# CANNode.net
KiCad netlist of a schematic drawn in EAGLE
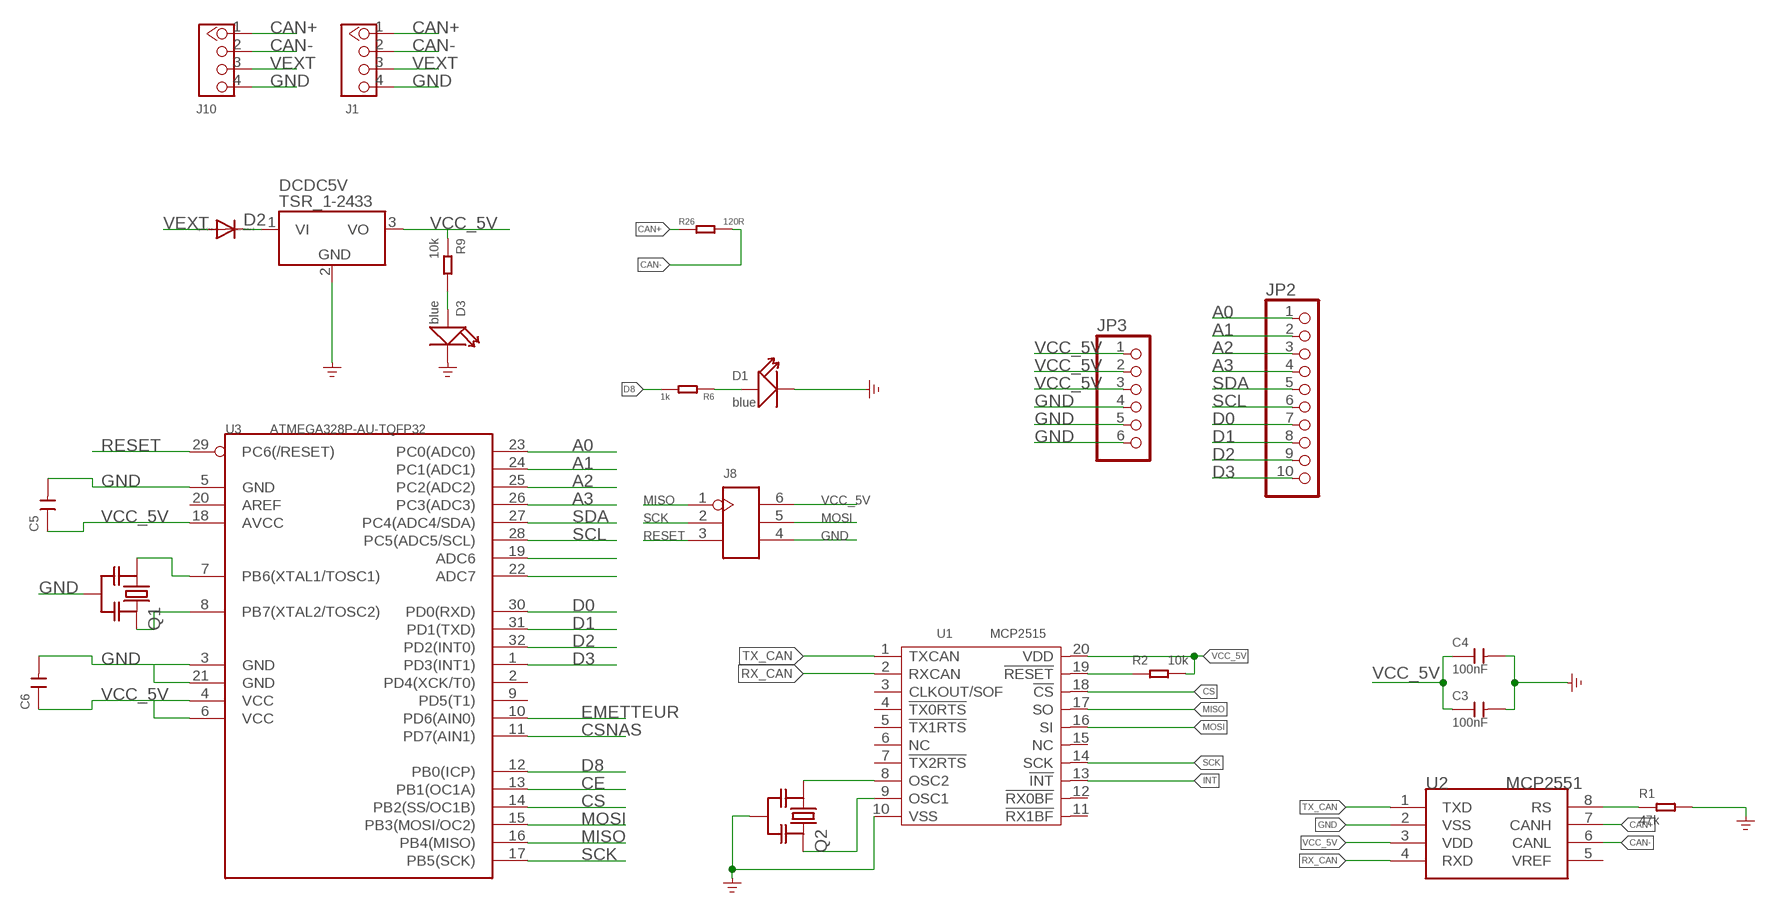
[diagram p0: schematic, sheet 1]

(export (version "E")
  (design (tool "Eeschema 10.0.6"))
  (components
    (comp (ref "C3")
      (value "100nF")
      (footprint "eagle-import:C0805")
      (libsource (lib "eagle-import") (part "CAP-0805"))
    )
    (comp (ref "C4")
      (value "100nF")
      (footprint "eagle-import:C0805")
      (libsource (lib "eagle-import") (part "CAP-0805"))
    )
    (comp (ref "C5")
      (value "CAP-0805")
      (footprint "eagle-import:C0805")
      (libsource (lib "eagle-import") (part "CAP-0805"))
    )
    (comp (ref "C6")
      (value "CAP-0805")
      (footprint "eagle-import:C0805")
      (libsource (lib "eagle-import") (part "CAP-0805"))
    )
    (comp (ref "D1")
      (value "blue")
      (footprint "eagle-import:LED-0805")
      (libsource (lib "eagle-import") (part "LED-0805"))
    )
    (comp (ref "D2")
      (value "DIODE-SOD323-W")
      (footprint "eagle-import:SOD323-W")
      (libsource (lib "eagle-import") (part "DIODE-SOD323-W"))
    )
    (comp (ref "D3")
      (value "blue")
      (footprint "eagle-import:LED-0805")
      (libsource (lib "eagle-import") (part "LED-0805"))
    )
    (comp (ref "DCDC5V")
      (value "TSR_1-2433")
      (footprint "eagle-import:TSR-1")
      (libsource (lib "eagle-import") (part "TSR_1-2433"))
    )
    (comp (ref "J1")
      (value "320110033")
      (footprint "eagle-import:HW4-2.0")
      (libsource (lib "eagle-import") (part "GROVE-CONNECTOR-DIP-2.0"))
    )
    (comp (ref "J8")
      (value "HEADER-2X3P-2.54")
      (footprint "eagle-import:H2X3-2.54")
      (libsource (lib "eagle-import") (part "HEADER-2X3P-2.54"))
    )
    (comp (ref "J10")
      (value "320110033")
      (footprint "eagle-import:HW4-2.0")
      (libsource (lib "eagle-import") (part "GROVE-CONNECTOR-DIP-2.0"))
    )
    (comp (ref "JP2")
      (value "PINHD-1X10")
      (footprint "eagle-import:1X10")
      (libsource (lib "eagle-import") (part "PINHD-1X10"))
    )
    (comp (ref "JP3")
      (value "PINHD-1X6")
      (footprint "eagle-import:1X06")
      (libsource (lib "eagle-import") (part "PINHD-1X6"))
    )
    (comp (ref "Q1")
      (value "RESONATOR-MURATACST_CE")
      (footprint "eagle-import:RESONATOR_MURATA2")
      (libsource (lib "eagle-import") (part "RESONATOR-MURATACST_CE"))
    )
    (comp (ref "Q2")
      (value "RESONATOR-MURATACST_CE")
      (footprint "eagle-import:RESONATOR_MURATA2")
      (libsource (lib "eagle-import") (part "RESONATOR-MURATACST_CE"))
    )
    (comp (ref "R1")
      (value "47k")
      (footprint "eagle-import:R0805")
      (libsource (lib "eagle-import") (part "Seeed-OPL-Resistor_RES-0805"))
    )
    (comp (ref "R2")
      (value "10k")
      (footprint "eagle-import:R0603")
      (libsource (lib "eagle-import") (part "RES-0603"))
    )
    (comp (ref "R6")
      (value "1k")
      (footprint "eagle-import:R0805")
      (libsource (lib "eagle-import") (part "Seeed-OPL-Resistor_RES-0805"))
    )
    (comp (ref "R9")
      (value "10k")
      (footprint "eagle-import:R0805")
      (libsource (lib "eagle-import") (part "Seeed-OPL-Resistor_RES-0805"))
    )
    (comp (ref "R26")
      (value "120R")
      (footprint "eagle-import:R0805")
      (libsource (lib "eagle-import") (part "Seeed-OPL-Resistor_RES-0805"))
    )
    (comp (ref "U1")
      (value "MCP2515")
      (footprint "eagle-import:TSSOP20-0.65-6.5X4.4MM")
      (libsource (lib "eagle-import") (part "MCP2515'ST'"))
    )
    (comp (ref "U2")
      (value "MCP2551")
      (footprint "eagle-import:SOIC8-6.0")
      (libsource (lib "eagle-import") (part "MCP2551-SOIC8"))
    )
    (comp (ref "U3")
      (value "ATMEGA328P-AU-TQFP32")
      (footprint "eagle-import:TQFP32-0.8-7X7MM")
      (fields (field (name "MPN") "ATMEGA328P-AU"))
      (libsource (lib "eagle-import") (part "MCU-ATMEGA328P-AU(TQFP32)"))
    )
  )
  (nets
    (net (code "1") (name "A0") (class "Default")
      (node (ref "JP2") (pin "1") (pinfunction "1_1") (pintype "passive"))
      (node (ref "U3") (pin "23") (pinfunction "PC0(ADC0)_23") (pintype "bidirectional"))
    )
    (net (code "2") (name "A1") (class "Default")
      (node (ref "JP2") (pin "2") (pinfunction "2_2") (pintype "passive"))
      (node (ref "U3") (pin "24") (pinfunction "PC1(ADC1)_24") (pintype "bidirectional"))
    )
    (net (code "3") (name "A2") (class "Default")
      (node (ref "JP2") (pin "3") (pinfunction "3_3") (pintype "passive"))
      (node (ref "U3") (pin "25") (pinfunction "PC2(ADC2)_25") (pintype "bidirectional"))
    )
    (net (code "4") (name "A3") (class "Default")
      (node (ref "JP2") (pin "4") (pinfunction "4_4") (pintype "passive"))
      (node (ref "U3") (pin "26") (pinfunction "PC3(ADC3)_26") (pintype "bidirectional"))
    )
    (net (code "5") (name "CAN+") (class "Default")
      (node (ref "J1") (pin "1") (pinfunction "1_1") (pintype "bidirectional"))
      (node (ref "J10") (pin "1") (pinfunction "1_1") (pintype "bidirectional"))
      (node (ref "R26") (pin "1") (pinfunction "1_1") (pintype "passive"))
      (node (ref "U2") (pin "7") (pinfunction "CANH_7") (pintype "bidirectional"))
    )
    (net (code "6") (name "CAN-") (class "Default")
      (node (ref "J1") (pin "2") (pinfunction "2_2") (pintype "bidirectional"))
      (node (ref "J10") (pin "2") (pinfunction "2_2") (pintype "bidirectional"))
      (node (ref "R26") (pin "2") (pinfunction "2_2") (pintype "passive"))
      (node (ref "U2") (pin "6") (pinfunction "CANL_6") (pintype "bidirectional"))
    )
    (net (code "7") (name "CE") (class "Default")
      (node (ref "U3") (pin "13") (pinfunction "PB1(OC1A)_13") (pintype "bidirectional"))
    )
    (net (code "8") (name "CS") (class "Default")
      (node (ref "U1") (pin "18") (pinfunction "~{CS}_18") (pintype "bidirectional"))
      (node (ref "U3") (pin "14") (pinfunction "PB2(SS/OC1B)_14") (pintype "bidirectional"))
    )
    (net (code "9") (name "CSNAS") (class "Default")
      (node (ref "U3") (pin "11") (pinfunction "PD7(AIN1)_11") (pintype "bidirectional"))
    )
    (net (code "10") (name "D0") (class "Default")
      (node (ref "JP2") (pin "7") (pinfunction "7_7") (pintype "passive"))
      (node (ref "U3") (pin "30") (pinfunction "PD0(RXD)_30") (pintype "bidirectional"))
    )
    (net (code "11") (name "D1") (class "Default")
      (node (ref "JP2") (pin "8") (pinfunction "8_8") (pintype "passive"))
      (node (ref "U3") (pin "31") (pinfunction "PD1(TXD)_31") (pintype "bidirectional"))
    )
    (net (code "12") (name "D2") (class "Default")
      (node (ref "JP2") (pin "9") (pinfunction "9_9") (pintype "passive"))
      (node (ref "U3") (pin "32") (pinfunction "PD2(INT0)_32") (pintype "bidirectional"))
    )
    (net (code "13") (name "D3") (class "Default")
      (node (ref "JP2") (pin "10") (pinfunction "10_10") (pintype "passive"))
      (node (ref "U3") (pin "1") (pinfunction "PD3(INT1)_1") (pintype "bidirectional"))
    )
    (net (code "14") (name "D8") (class "Default")
      (node (ref "R6") (pin "2") (pinfunction "2_2") (pintype "passive"))
      (node (ref "U3") (pin "12") (pinfunction "PB0(ICP)_12") (pintype "bidirectional"))
    )
    (net (code "15") (name "EMETTEUR") (class "Default")
      (node (ref "U3") (pin "10") (pinfunction "PD6(AIN0)_10") (pintype "bidirectional"))
    )
    (net (code "16") (name "GND") (class "Default")
      (node (ref "C3") (pin "2") (pinfunction "2_2") (pintype "passive"))
      (node (ref "C4") (pin "2") (pinfunction "2_2") (pintype "passive"))
      (node (ref "C5") (pin "2") (pinfunction "2_2") (pintype "passive"))
      (node (ref "C6") (pin "2") (pinfunction "2_2") (pintype "passive"))
      (node (ref "D1") (pin "-") (pinfunction "-_-") (pintype "passive"))
      (node (ref "D3") (pin "-") (pinfunction "-_-") (pintype "passive"))
      (node (ref "DCDC5V") (pin "2") (pinfunction "GND_2") (pintype "power_in"))
      (node (ref "J1") (pin "4") (pinfunction "4_4") (pintype "bidirectional"))
      (node (ref "J10") (pin "4") (pinfunction "4_4") (pintype "bidirectional"))
      (node (ref "J8") (pin "4") (pinfunction "4_4") (pintype "bidirectional"))
      (node (ref "JP3") (pin "4") (pinfunction "4_4") (pintype "passive"))
      (node (ref "JP3") (pin "5") (pinfunction "5_5") (pintype "passive"))
      (node (ref "JP3") (pin "6") (pinfunction "6_6") (pintype "passive"))
      (node (ref "Q1") (pin "2") (pinfunction "2_2") (pintype "passive"))
      (node (ref "Q2") (pin "2") (pinfunction "2_2") (pintype "passive"))
      (node (ref "R1") (pin "2") (pinfunction "2_2") (pintype "passive"))
      (node (ref "U1") (pin "10") (pinfunction "VSS_10") (pintype "bidirectional"))
      (node (ref "U2") (pin "2") (pinfunction "VSS_2") (pintype "bidirectional"))
      (node (ref "U3") (pin "21") (pinfunction "GND_21") (pintype "bidirectional"))
      (node (ref "U3") (pin "3") (pinfunction "GND_3") (pintype "bidirectional"))
      (node (ref "U3") (pin "5") (pinfunction "GND_5") (pintype "bidirectional"))
    )
    (net (code "17") (name "INT") (class "Default")
      (node (ref "U1") (pin "13") (pinfunction "~{INT}_13") (pintype "bidirectional"))
    )
    (net (code "18") (name "MISO") (class "Default")
      (node (ref "J8") (pin "1") (pinfunction "1_1") (pintype "bidirectional"))
      (node (ref "U1") (pin "17") (pinfunction "SO_17") (pintype "bidirectional"))
      (node (ref "U3") (pin "16") (pinfunction "PB4(MISO)_16") (pintype "bidirectional"))
    )
    (net (code "19") (name "MOSI") (class "Default")
      (node (ref "J8") (pin "5") (pinfunction "5_5") (pintype "bidirectional"))
      (node (ref "U1") (pin "16") (pinfunction "SI_16") (pintype "bidirectional"))
      (node (ref "U3") (pin "15") (pinfunction "PB3(MOSI/OC2)_15") (pintype "bidirectional"))
    )
    (net (code "20") (name "Net-(D1-Pad+)") (class "Default")
      (node (ref "D1") (pin "+") (pinfunction "+_+") (pintype "passive"))
      (node (ref "R6") (pin "1") (pinfunction "1_1") (pintype "passive"))
    )
    (net (code "21") (name "Net-(D3-Pad+)") (class "Default")
      (node (ref "D3") (pin "+") (pinfunction "+_+") (pintype "passive"))
      (node (ref "R9") (pin "2") (pinfunction "2_2") (pintype "passive"))
    )
    (net (code "22") (name "Net-(DCDC5V-VI)") (class "Default")
      (node (ref "D2") (pin "C") (pinfunction "C_C") (pintype "passive"))
      (node (ref "DCDC5V") (pin "1") (pinfunction "VI_1") (pintype "power_in"))
    )
    (net (code "23") (name "Net-(U1-OSC1)") (class "Default")
      (node (ref "Q2") (pin "3") (pinfunction "3_3") (pintype "passive"))
      (node (ref "U1") (pin "9") (pinfunction "OSC1_9") (pintype "bidirectional"))
    )
    (net (code "24") (name "Net-(U1-OSC2)") (class "Default")
      (node (ref "Q2") (pin "1") (pinfunction "1_1") (pintype "passive"))
      (node (ref "U1") (pin "8") (pinfunction "OSC2_8") (pintype "bidirectional"))
    )
    (net (code "25") (name "Net-(U1-~{RESET})") (class "Default")
      (node (ref "R2") (pin "1") (pinfunction "1_1") (pintype "passive"))
      (node (ref "U1") (pin "19") (pinfunction "~{RESET}_19") (pintype "bidirectional"))
    )
    (net (code "26") (name "Net-(U2-RS)") (class "Default")
      (node (ref "R1") (pin "1") (pinfunction "1_1") (pintype "passive"))
      (node (ref "U2") (pin "8") (pinfunction "RS_8") (pintype "bidirectional"))
    )
    (net (code "27") (name "Net-(U3-PB6(XTAL1{slash}TOSC1))") (class "Default")
      (node (ref "Q1") (pin "1") (pinfunction "1_1") (pintype "passive"))
      (node (ref "U3") (pin "7") (pinfunction "PB6(XTAL1/TOSC1)_7") (pintype "bidirectional"))
    )
    (net (code "28") (name "Net-(U3-PB7(XTAL2{slash}TOSC2))") (class "Default")
      (node (ref "Q1") (pin "3") (pinfunction "3_3") (pintype "passive"))
      (node (ref "U3") (pin "8") (pinfunction "PB7(XTAL2/TOSC2)_8") (pintype "bidirectional"))
    )
    (net (code "29") (name "RESET") (class "Default")
      (node (ref "J8") (pin "3") (pinfunction "3_3") (pintype "bidirectional"))
      (node (ref "U3") (pin "29") (pinfunction "PC6(/RESET)_29") (pintype "bidirectional"))
    )
    (net (code "30") (name "RX_CAN") (class "Default")
      (node (ref "U1") (pin "2") (pinfunction "RXCAN_2") (pintype "bidirectional"))
      (node (ref "U2") (pin "4") (pinfunction "RXD_4") (pintype "bidirectional"))
    )
    (net (code "31") (name "SCK") (class "Default")
      (node (ref "J8") (pin "2") (pinfunction "2_2") (pintype "bidirectional"))
      (node (ref "U1") (pin "14") (pinfunction "SCK_14") (pintype "bidirectional"))
      (node (ref "U3") (pin "17") (pinfunction "PB5(SCK)_17") (pintype "bidirectional"))
    )
    (net (code "32") (name "SCL") (class "Default")
      (node (ref "JP2") (pin "6") (pinfunction "6_6") (pintype "passive"))
      (node (ref "U3") (pin "28") (pinfunction "PC5(ADC5/SCL)_28") (pintype "bidirectional"))
    )
    (net (code "33") (name "SDA") (class "Default")
      (node (ref "JP2") (pin "5") (pinfunction "5_5") (pintype "passive"))
      (node (ref "U3") (pin "27") (pinfunction "PC4(ADC4/SDA)_27") (pintype "bidirectional"))
    )
    (net (code "34") (name "TX_CAN") (class "Default")
      (node (ref "U1") (pin "1") (pinfunction "TXCAN_1") (pintype "bidirectional"))
      (node (ref "U2") (pin "1") (pinfunction "TXD_1") (pintype "bidirectional"))
    )
    (net (code "35") (name "VCC_5V") (class "Default")
      (node (ref "C3") (pin "1") (pinfunction "1_1") (pintype "passive"))
      (node (ref "C4") (pin "1") (pinfunction "1_1") (pintype "passive"))
      (node (ref "C5") (pin "1") (pinfunction "1_1") (pintype "passive"))
      (node (ref "C6") (pin "1") (pinfunction "1_1") (pintype "passive"))
      (node (ref "DCDC5V") (pin "3") (pinfunction "VO_3") (pintype "power_in"))
      (node (ref "J8") (pin "6") (pinfunction "6_6") (pintype "bidirectional"))
      (node (ref "JP3") (pin "1") (pinfunction "1_1") (pintype "passive"))
      (node (ref "JP3") (pin "2") (pinfunction "2_2") (pintype "passive"))
      (node (ref "JP3") (pin "3") (pinfunction "3_3") (pintype "passive"))
      (node (ref "R2") (pin "2") (pinfunction "2_2") (pintype "passive"))
      (node (ref "R9") (pin "1") (pinfunction "1_1") (pintype "passive"))
      (node (ref "U1") (pin "20") (pinfunction "VDD_20") (pintype "bidirectional"))
      (node (ref "U2") (pin "3") (pinfunction "VDD_3") (pintype "bidirectional"))
      (node (ref "U3") (pin "18") (pinfunction "AVCC_18") (pintype "bidirectional"))
      (node (ref "U3") (pin "4") (pinfunction "VCC_4") (pintype "bidirectional"))
      (node (ref "U3") (pin "6") (pinfunction "VCC_6") (pintype "bidirectional"))
    )
    (net (code "36") (name "VEXT") (class "Default")
      (node (ref "D2") (pin "A") (pinfunction "A_A") (pintype "passive"))
      (node (ref "J1") (pin "3") (pinfunction "3_3") (pintype "bidirectional"))
      (node (ref "J10") (pin "3") (pinfunction "3_3") (pintype "bidirectional"))
    )
    (net (code "37") (name "unconnected-(U1-CLKOUT{slash}SOF-Pad3)") (class "Default")
      (node (ref "U1") (pin "3") (pinfunction "CLKOUT/SOF_3") (pintype "bidirectional"))
    )
    (net (code "38") (name "unconnected-(U1-NC-Pad6)") (class "Default")
      (node (ref "U1") (pin "6") (pinfunction "NC_6") (pintype "bidirectional"))
    )
    (net (code "39") (name "unconnected-(U1-NC-Pad15)") (class "Default")
      (node (ref "U1") (pin "15") (pinfunction "NC_15") (pintype "bidirectional"))
    )
    (net (code "40") (name "unconnected-(U1-~{RX0BF}-Pad12)") (class "Default")
      (node (ref "U1") (pin "12") (pinfunction "~{RX0BF}_12") (pintype "bidirectional"))
    )
    (net (code "41") (name "unconnected-(U1-~{RX1BF}-Pad11)") (class "Default")
      (node (ref "U1") (pin "11") (pinfunction "~{RX1BF}_11") (pintype "bidirectional"))
    )
    (net (code "42") (name "unconnected-(U1-~{TX0RTS}-Pad4)") (class "Default")
      (node (ref "U1") (pin "4") (pinfunction "~{TX0RTS}_4") (pintype "bidirectional"))
    )
    (net (code "43") (name "unconnected-(U1-~{TX1RTS}-Pad5)") (class "Default")
      (node (ref "U1") (pin "5") (pinfunction "~{TX1RTS}_5") (pintype "bidirectional"))
    )
    (net (code "44") (name "unconnected-(U1-~{TX2RTS}-Pad7)") (class "Default")
      (node (ref "U1") (pin "7") (pinfunction "~{TX2RTS}_7") (pintype "bidirectional"))
    )
    (net (code "45") (name "unconnected-(U2-VREF-Pad5)") (class "Default")
      (node (ref "U2") (pin "5") (pinfunction "VREF_5") (pintype "bidirectional"))
    )
    (net (code "46") (name "unconnected-(U3-ADC6-Pad19)") (class "Default")
      (node (ref "U3") (pin "19") (pinfunction "ADC6_19") (pintype "bidirectional"))
    )
    (net (code "47") (name "unconnected-(U3-ADC7-Pad22)") (class "Default")
      (node (ref "U3") (pin "22") (pinfunction "ADC7_22") (pintype "bidirectional"))
    )
    (net (code "48") (name "unconnected-(U3-AREF-Pad20)") (class "Default")
      (node (ref "U3") (pin "20") (pinfunction "AREF_20") (pintype "bidirectional"))
    )
    (net (code "49") (name "unconnected-(U3-PD4(XCK{slash}T0)-Pad2)") (class "Default")
      (node (ref "U3") (pin "2") (pinfunction "PD4(XCK/T0)_2") (pintype "bidirectional"))
    )
    (net (code "50") (name "unconnected-(U3-PD5(T1)-Pad9)") (class "Default")
      (node (ref "U3") (pin "9") (pinfunction "PD5(T1)_9") (pintype "bidirectional"))
    )
  )
)
